# HV_DRV_Discrete.net
KiCad netlist of a schematic drawn in Altium Designer
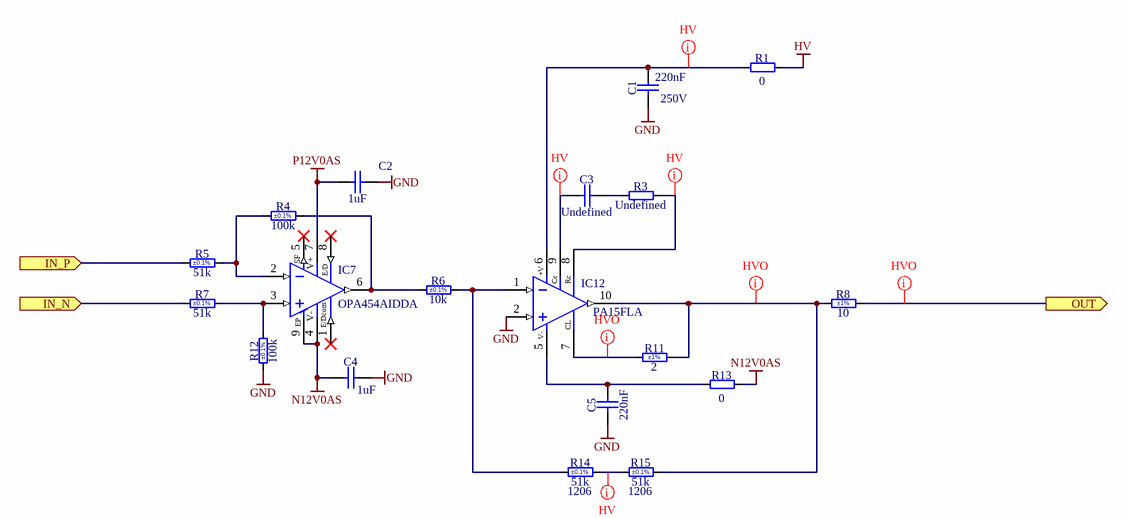
[diagram p0: HV_DRV_Discrete.SchDoc]

(export (version "E")
  (design (tool "Eeschema 10.0.6"))
  (components
    (comp (ref "C1")
      (value "220nF")
      (footprint "CAPC4532X165N")
      (description "Non-polarised capacitor")
      (fields
        (field (name "PART NUMBER") "CC1812_220NF_250V_10%_X7R_FT-CAP")
        (field (name "VOLTAGE") "250V")
        (field (name "TOLERANCE") "±10%")
        (field (name "AUTHOR") "CERN DEM JLC")
      )
      (libsource (lib "Capacitors") (part "Capacitor - non polarized"))
    )
    (comp (ref "C2")
      (value "1uF")
      (footprint "CAPC1608X87N")
      (description "Non-polarised capacitor")
      (fields
        (field (name "PART NUMBER") "CC0603_1UF_50V_10%_X5R")
        (field (name "VOLTAGE") "50V")
        (field (name "AUTHOR") "CERN DEM JMW")
      )
      (libsource (lib "Capacitors") (part "Capacitor - non polarized"))
    )
    (comp (ref "C3")
      (value "Undefined")
      (footprint "CAPC3216X140N")
      (description "Non-polarised capacitor")
      (fields (field (name "PART NUMBER") "CC1206_NO-VALUE") (field (name "AUTHOR") "CERN DEM JLC"))
      (libsource (lib "Capacitors") (part "Capacitor - non polarized"))
    )
    (comp (ref "C4")
      (value "1uF")
      (footprint "CAPC1608X87N")
      (description "Non-polarised capacitor")
      (fields
        (field (name "PART NUMBER") "CC0603_1UF_50V_10%_X5R")
        (field (name "VOLTAGE") "50V")
        (field (name "AUTHOR") "CERN DEM JMW")
      )
      (libsource (lib "Capacitors") (part "Capacitor - non polarized"))
    )
    (comp (ref "C5")
      (value "220nF")
      (footprint "CAPC1608X87N")
      (description "Non-polarised capacitor")
      (fields
        (field (name "PART NUMBER") "CC0603_220NF_25V_10%_X7R")
        (field (name "VOLTAGE") "25V")
        (field (name "AUTHOR") "CERN DEM JLC")
      )
      (libsource (lib "Capacitors") (part "Capacitor - non polarized"))
    )
    (comp (ref "IC7")
      (value "OPA454AIDDA")
      (footprint "SOIC127P600X170-9N-R249X300")
      (description "High-Voltage (100V), High-Current (50mA) Operational Amplifier, G=1 Stable")
      (fields (field (name "MANUFACTURER") "TEXAS INSTRUMENTS") (field (name "AUTHOR") "CERN DEM JLC"))
      (libsource (lib "ICs And Semiconductors") (part "OPA454"))
    )
    (comp (ref "IC12")
      (value "PA15FLA")
      (footprint "APEX_PA15FL_v")
      (description "High Voltage Power Operational Amplifier")
      (fields
        (field (name "PART NUMBER") "PA15FLA_v")
        (field (name "MANUFACTURER") "APEX MICROTECHNOLOGY")
        (field (name "AUTHOR") "CERN DEM BC")
      )
      (libsource (lib "ICs And Semiconductors") (part "PA15"))
    )
    (comp (ref "R1")
      (value "0")
      (footprint "RESC1608X55N")
      (description "Resistor")
      (fields
        (field (name "PART NUMBER") "R0603_0R_JUMPER")
        (field (name "MANUFACTURER") "GENERIC")
        (field (name "AUTHOR") "CERN DEM JLC")
      )
      (libsource (lib "Resistors") (part "Resistor"))
    )
    (comp (ref "R3")
      (value "Undefined")
      (footprint "RESC3216X65N")
      (description "Resistor")
      (fields (field (name "PART NUMBER") "R1206_NO-VALUE") (field (name "AUTHOR") "CERN DEM JLC"))
      (libsource (lib "Resistors") (part "Resistor"))
    )
    (comp (ref "R4")
      (value "100k")
      (footprint "RESC1608X55N")
      (description "Resistor - 0.1%")
      (fields
        (field (name "TOLERANCE") "±0.1%")
        (field (name "PART NUMBER") "R0603_100K_0.1%_0.063W_10PPM")
        (field (name "POWER") "0.063W")
        (field (name "AUTHOR") "CERN DEM JLC")
      )
      (libsource (lib "Resistors") (part "Resistor - 0.1%"))
    )
    (comp (ref "R5")
      (value "51k")
      (footprint "RESC2012X60N")
      (description "Resistor - 0.1%")
      (fields
        (field (name "TOLERANCE") "±0.1%")
        (field (name "PART NUMBER") "R0805_51K_0.1%_0.125W_10PPM")
        (field (name "POWER") "0.125W")
        (field (name "AUTHOR") "CERN DEM BC")
      )
      (libsource (lib "Resistors") (part "Resistor - 0.1%"))
    )
    (comp (ref "R6")
      (value "10k")
      (footprint "RESC1608X64N")
      (description "Resistor - 0.1%")
      (fields
        (field (name "TOLERANCE") "±0.1%")
        (field (name "PART NUMBER") "R0603_10K_0.1%_0.1W_25PPM")
        (field (name "POWER") "0.1W")
        (field (name "AUTHOR") "CERN DEM JMW")
      )
      (libsource (lib "Resistors") (part "Resistor - 0.1%"))
    )
    (comp (ref "R7")
      (value "51k")
      (footprint "RESC2012X60N")
      (description "Resistor - 0.1%")
      (fields
        (field (name "TOLERANCE") "±0.1%")
        (field (name "PART NUMBER") "R0805_51K_0.1%_0.125W_10PPM")
        (field (name "POWER") "0.125W")
        (field (name "AUTHOR") "CERN DEM BC")
      )
      (libsource (lib "Resistors") (part "Resistor - 0.1%"))
    )
    (comp (ref "R8")
      (value "10")
      (footprint "RESC3216X65N")
      (description "Resistor - 1%")
      (fields
        (field (name "TOLERANCE") "±1%")
        (field (name "PART NUMBER") "R1206_10R_1%_0.25W_200PPM")
        (field (name "POWER") "0.25W")
        (field (name "AUTHOR") "CERN DEM JLC")
      )
      (libsource (lib "Resistors") (part "Resistor - 1%"))
    )
    (comp (ref "R11")
      (value "2")
      (footprint "RESC1608X55N")
      (description "Resistor - 1%")
      (fields
        (field (name "TOLERANCE") "±1%")
        (field (name "PART NUMBER") "R0603_2R_1%_0.1W_200PPM")
        (field (name "POWER") "0.1W")
        (field (name "AUTHOR") "CERN DEM JLC")
      )
      (libsource (lib "Resistors") (part "Resistor - 1%"))
    )
    (comp (ref "R12")
      (value "100k")
      (footprint "RESC1608X55N")
      (description "Resistor - 0.1%")
      (fields
        (field (name "TOLERANCE") "±0.1%")
        (field (name "PART NUMBER") "R0603_100K_0.1%_0.063W_10PPM")
        (field (name "POWER") "0.063W")
        (field (name "AUTHOR") "CERN DEM JLC")
      )
      (libsource (lib "Resistors") (part "Resistor - 0.1%"))
    )
    (comp (ref "R13")
      (value "0")
      (footprint "RESC1608X55N")
      (description "Resistor")
      (fields
        (field (name "PART NUMBER") "R0603_0R_JUMPER")
        (field (name "MANUFACTURER") "GENERIC")
        (field (name "AUTHOR") "CERN DEM JLC")
      )
      (libsource (lib "Resistors") (part "Resistor"))
    )
    (comp (ref "R14")
      (value "51k")
      (footprint "RESC3216X65N")
      (description "Resistor - 0.1%")
      (fields
        (field (name "TOLERANCE") "±0.1%")
        (field (name "PART NUMBER") "R1206_51K_0.1%_0.25W_25PPM")
        (field (name "POWER") "0.25W")
        (field (name "CASE") "1206")
        (field (name "AUTHOR") "CERN DEM JLC")
      )
      (libsource (lib "Resistors") (part "Resistor - 0.1%"))
    )
    (comp (ref "R15")
      (value "51k")
      (footprint "RESC3216X65N")
      (description "Resistor - 0.1%")
      (fields
        (field (name "TOLERANCE") "±0.1%")
        (field (name "PART NUMBER") "R1206_51K_0.1%_0.25W_25PPM")
        (field (name "POWER") "0.25W")
        (field (name "CASE") "1206")
        (field (name "AUTHOR") "CERN DEM JLC")
      )
      (libsource (lib "Resistors") (part "Resistor - 0.1%"))
    )
  )
  (nets
    (net (code "1") (name "/IN_N") (class "Default")
      (node (ref "R7") (pin "1") (pinfunction "1_1") (pintype "passive"))
    )
    (net (code "2") (name "/IN_P") (class "Default")
      (node (ref "R5") (pin "1") (pinfunction "1_1") (pintype "passive"))
    )
    (net (code "3") (name "/OUT") (class "Default")
      (node (ref "R8") (pin "2") (pinfunction "2_2") (pintype "passive"))
    )
    (net (code "4") (name "GND") (class "Default")
      (node (ref "C1") (pin "1") (pinfunction "1_1") (pintype "passive"))
      (node (ref "C2") (pin "2") (pinfunction "2_2") (pintype "passive"))
      (node (ref "C4") (pin "2") (pinfunction "2_2") (pintype "passive"))
      (node (ref "C5") (pin "1") (pinfunction "1_1") (pintype "passive"))
      (node (ref "IC12") (pin "2") (pinfunction "IN+_2") (pintype "input"))
      (node (ref "R12") (pin "1") (pinfunction "1_1") (pintype "passive"))
    )
    (net (code "5") (name "HV") (class "Default")
      (node (ref "R1") (pin "2") (pinfunction "2_2") (pintype "passive"))
    )
    (net (code "6") (name "N12V0AS") (class "Default")
      (node (ref "C4") (pin "1") (pinfunction "1_1") (pintype "passive"))
      (node (ref "IC7") (pin "4") (pinfunction "V-_4") (pintype "power_in"))
      (node (ref "IC7") (pin "9") (pinfunction "Exposed_Pad_9") (pintype "power_in"))
      (node (ref "R13") (pin "2") (pinfunction "2_2") (pintype "passive"))
    )
    (net (code "7") (name "Net-(C3-Pad2)") (class "Default")
      (node (ref "C3") (pin "2") (pinfunction "2_2") (pintype "passive"))
      (node (ref "R3") (pin "1") (pinfunction "1_1") (pintype "passive"))
    )
    (net (code "8") (name "Net-(IC7-IN+)") (class "Default")
      (node (ref "IC7") (pin "3") (pinfunction "IN+_3") (pintype "input"))
      (node (ref "R12") (pin "2") (pinfunction "2_2") (pintype "passive"))
      (node (ref "R7") (pin "2") (pinfunction "2_2") (pintype "passive"))
    )
    (net (code "9") (name "Net-(IC7-IN-)") (class "Default")
      (node (ref "IC7") (pin "2") (pinfunction "IN-_2") (pintype "input"))
      (node (ref "R4") (pin "1") (pinfunction "1_1") (pintype "passive"))
      (node (ref "R5") (pin "2") (pinfunction "2_2") (pintype "passive"))
    )
    (net (code "10") (name "Net-(IC7-OUT)") (class "Default")
      (node (ref "IC7") (pin "6") (pinfunction "OUT_6") (pintype "output"))
      (node (ref "R4") (pin "2") (pinfunction "2_2") (pintype "passive"))
      (node (ref "R6") (pin "1") (pinfunction "1_1") (pintype "passive"))
    )
    (net (code "11") (name "Net-(IC12-+Vs)") (class "Default")
      (node (ref "C1") (pin "2") (pinfunction "2_2") (pintype "passive"))
      (node (ref "IC12") (pin "6") (pinfunction "+Vs_6") (pintype "power_in"))
      (node (ref "R1") (pin "1") (pinfunction "1_1") (pintype "passive"))
    )
    (net (code "12") (name "Net-(IC12--Vs)") (class "Default")
      (node (ref "C5") (pin "2") (pinfunction "2_2") (pintype "passive"))
      (node (ref "IC12") (pin "5") (pinfunction "-Vs_5") (pintype "power_in"))
      (node (ref "R13") (pin "1") (pinfunction "1_1") (pintype "passive"))
    )
    (net (code "13") (name "Net-(IC12-CL)") (class "Default")
      (node (ref "IC12") (pin "7") (pinfunction "CL_7") (pintype "passive"))
      (node (ref "R11") (pin "1") (pinfunction "1_1") (pintype "passive"))
    )
    (net (code "14") (name "Net-(IC12-Cc)") (class "Default")
      (node (ref "C3") (pin "1") (pinfunction "1_1") (pintype "passive"))
      (node (ref "IC12") (pin "9") (pinfunction "Cc_9") (pintype "passive"))
    )
    (net (code "15") (name "Net-(IC12-Cc2)") (class "Default")
      (node (ref "IC12") (pin "8") (pinfunction "Cc2_8") (pintype "passive"))
      (node (ref "R3") (pin "2") (pinfunction "2_2") (pintype "passive"))
    )
    (net (code "16") (name "Net-(IC12-IN-)") (class "Default")
      (node (ref "IC12") (pin "1") (pinfunction "IN-_1") (pintype "input"))
      (node (ref "R14") (pin "1") (pinfunction "1_1") (pintype "passive"))
      (node (ref "R6") (pin "2") (pinfunction "2_2") (pintype "passive"))
    )
    (net (code "17") (name "Net-(IC12-OUT)") (class "Default")
      (node (ref "IC12") (pin "10") (pinfunction "OUT_10") (pintype "output"))
      (node (ref "R11") (pin "2") (pinfunction "2_2") (pintype "passive"))
      (node (ref "R15") (pin "2") (pinfunction "2_2") (pintype "passive"))
      (node (ref "R8") (pin "1") (pinfunction "1_1") (pintype "passive"))
    )
    (net (code "18") (name "Net-(R14-Pad2)") (class "Default")
      (node (ref "R14") (pin "2") (pinfunction "2_2") (pintype "passive"))
      (node (ref "R15") (pin "1") (pinfunction "1_1") (pintype "passive"))
    )
    (net (code "19") (name "P12V0AS") (class "Default")
      (node (ref "C2") (pin "1") (pinfunction "1_1") (pintype "passive"))
      (node (ref "IC7") (pin "7") (pinfunction "V+_7") (pintype "power_in"))
    )
    (net (code "20") (name "unconnected-(IC7-E{slash}B-Pad8)") (class "Default")
      (node (ref "IC7") (pin "8") (pinfunction "E/B_8") (pintype "input+no_connect"))
    )
    (net (code "21") (name "unconnected-(IC7-E{slash}Dcommon-Pad1)") (class "Default")
      (node (ref "IC7") (pin "1") (pinfunction "E/Dcommon_1") (pintype "input+no_connect"))
    )
    (net (code "22") (name "unconnected-(IC7-Status_Flag-Pad5)") (class "Default")
      (node (ref "IC7") (pin "5") (pinfunction "Status_Flag_5") (pintype "output+no_connect"))
    )
  )
)
